# M182A.net
KiCad netlist of a schematic drawn in EAGLE
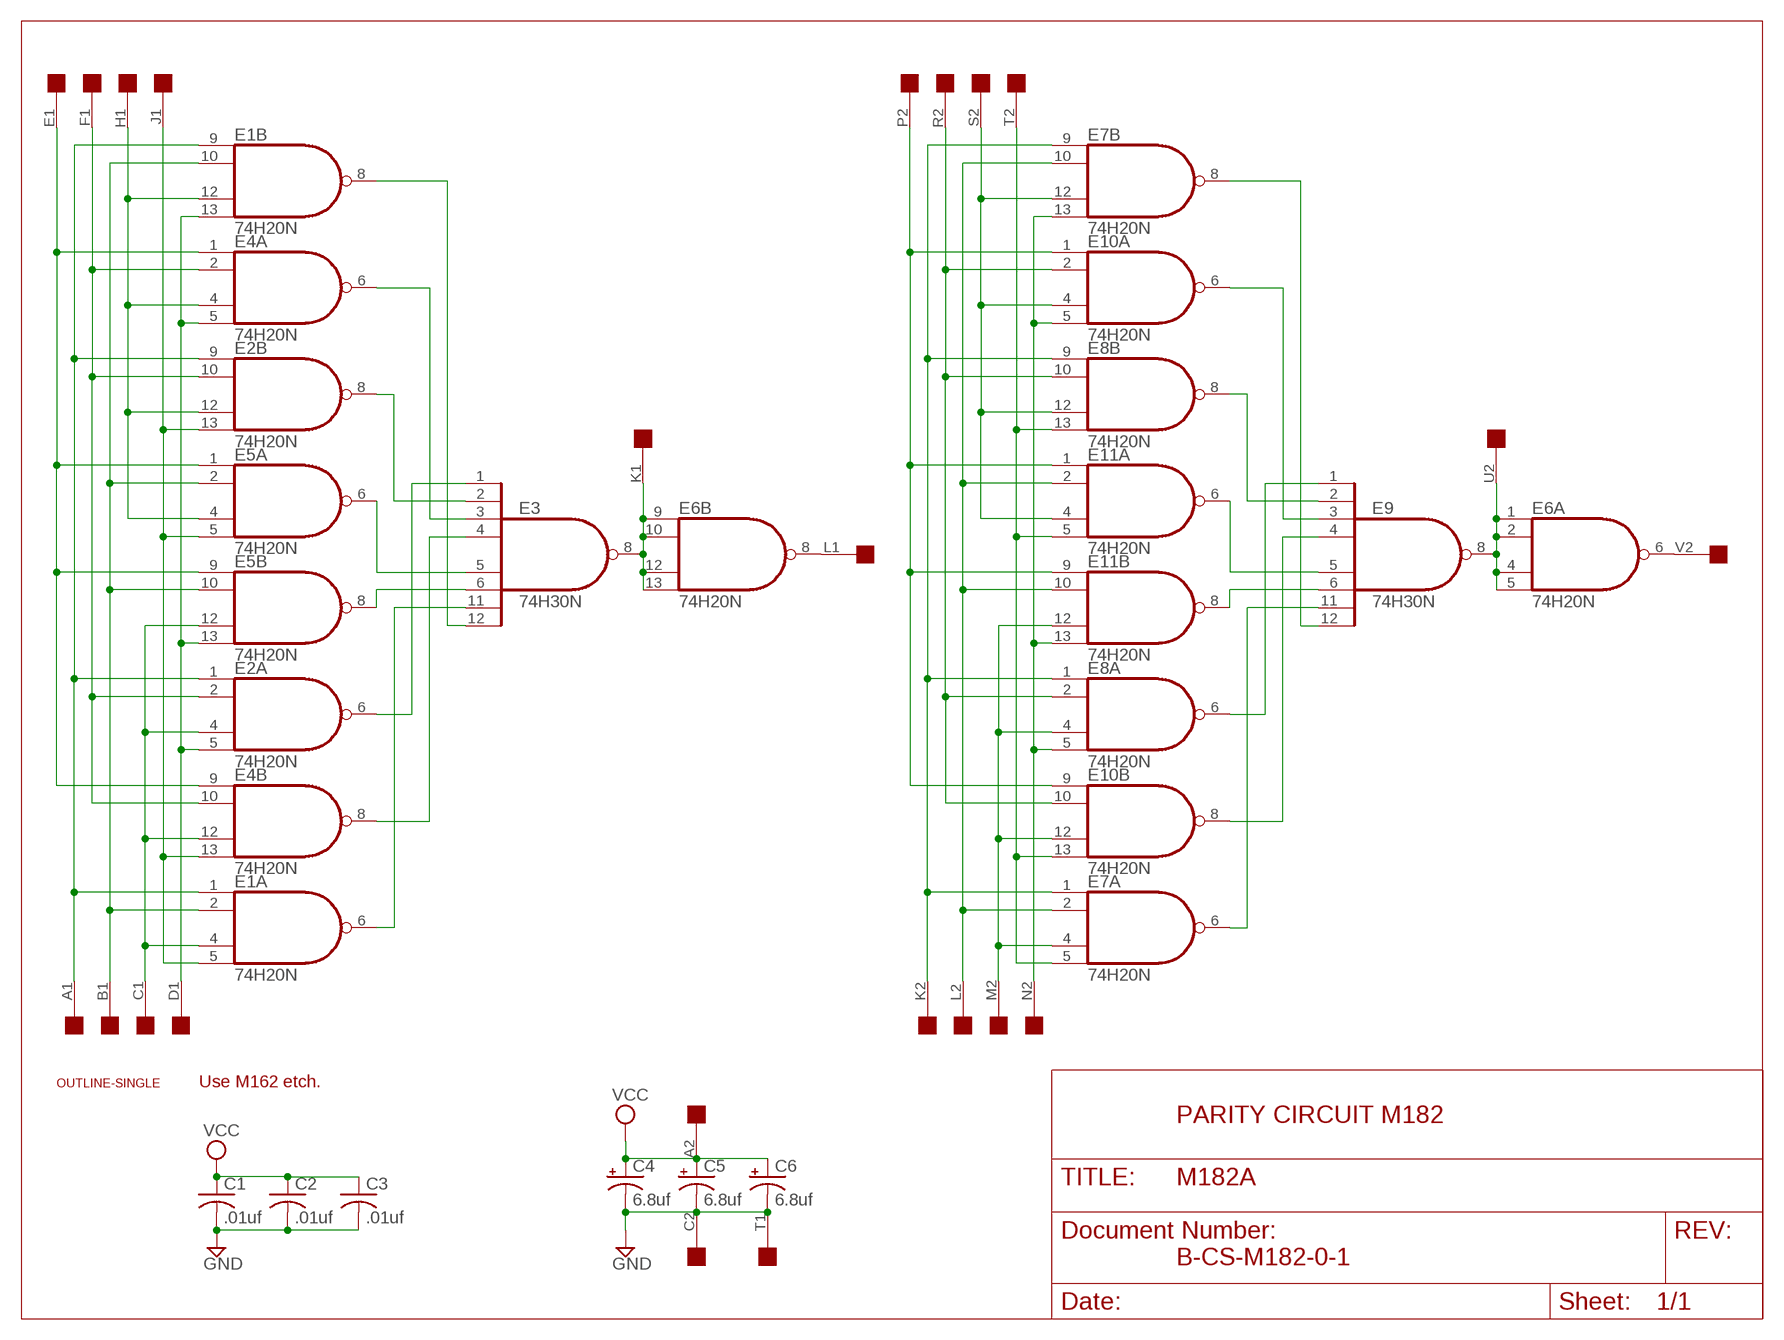
[diagram p0: schematic, sheet 1]

(export (version "E")
  (design (tool "Eeschema 10.0.6"))
  (components
    (comp (ref "C1")
      (value ".01uf")
      (footprint "eagle-import:C075-032X103")
      (libsource (lib "eagle-import") (part "C-US075-032X103"))
    )
    (comp (ref "C2")
      (value ".01uf")
      (footprint "eagle-import:C075-032X103")
      (libsource (lib "eagle-import") (part "C-US075-032X103"))
    )
    (comp (ref "C3")
      (value ".01uf")
      (footprint "eagle-import:C075-032X103")
      (libsource (lib "eagle-import") (part "C-US075-032X103"))
    )
    (comp (ref "C4")
      (value "6.8uf")
      (footprint "eagle-import:E15-5")
      (libsource (lib "eagle-import") (part "CPOL-USE15-5AXIAL"))
    )
    (comp (ref "C5")
      (value "6.8uf")
      (footprint "eagle-import:E15-5")
      (libsource (lib "eagle-import") (part "CPOL-USE15-5AXIAL"))
    )
    (comp (ref "C6")
      (value "6.8uf")
      (footprint "eagle-import:E15-5")
      (libsource (lib "eagle-import") (part "CPOL-USE15-5AXIAL"))
    )
    (comp (ref "E1")
      (value "74H20N")
      (footprint "eagle-import:DIL14")
      (libsource (lib "eagle-import") (part "7420NS"))
    )
    (comp (ref "E2")
      (value "74H20N")
      (footprint "eagle-import:DIL14")
      (libsource (lib "eagle-import") (part "7420NS"))
    )
    (comp (ref "E3")
      (value "74H30N")
      (footprint "eagle-import:DIL14")
      (libsource (lib "eagle-import") (part "7430N"))
    )
    (comp (ref "E4")
      (value "74H20N")
      (footprint "eagle-import:DIL14")
      (libsource (lib "eagle-import") (part "7420NS"))
    )
    (comp (ref "E5")
      (value "74H20N")
      (footprint "eagle-import:DIL14")
      (libsource (lib "eagle-import") (part "7420NS"))
    )
    (comp (ref "E6")
      (value "74H20N")
      (footprint "eagle-import:DIL14")
      (libsource (lib "eagle-import") (part "7420NS"))
    )
    (comp (ref "E7")
      (value "74H20N")
      (footprint "eagle-import:DIL14")
      (libsource (lib "eagle-import") (part "7420NS"))
    )
    (comp (ref "E8")
      (value "74H20N")
      (footprint "eagle-import:DIL14")
      (libsource (lib "eagle-import") (part "7420NS"))
    )
    (comp (ref "E9")
      (value "74H30N")
      (footprint "eagle-import:DIL14")
      (libsource (lib "eagle-import") (part "7430N"))
    )
    (comp (ref "E10")
      (value "74H20N")
      (footprint "eagle-import:DIL14")
      (libsource (lib "eagle-import") (part "7420NS"))
    )
    (comp (ref "E11")
      (value "74H20N")
      (footprint "eagle-import:DIL14")
      (libsource (lib "eagle-import") (part "7420NS"))
    )
    (comp (ref "U$1")
      (value "OUTLINE-SINGLE")
      (footprint "eagle-import:SINGLE")
      (libsource (lib "eagle-import") (part "OUTLINE-SINGLE"))
    )
    (comp (ref "U$2")
      (value "EDGE-2CONNECTOR")
      (footprint "eagle-import:EDGE-CON2")
      (libsource (lib "eagle-import") (part "EDGE-2CONNECTOR"))
    )
  )
  (nets
    (net (code "1") (name "GND") (class "Default")
      (node (ref "C1") (pin "2") (pinfunction "2_2") (pintype "passive"))
      (node (ref "C2") (pin "2") (pinfunction "2_2") (pintype "passive"))
      (node (ref "C3") (pin "2") (pinfunction "2_2") (pintype "passive"))
      (node (ref "C4") (pin "-") (pinfunction "-_-") (pintype "passive"))
      (node (ref "C5") (pin "-") (pinfunction "-_-") (pintype "passive"))
      (node (ref "C6") (pin "-") (pinfunction "-_-") (pintype "passive"))
      (node (ref "U$2") (pin "C2") (pinfunction "1_C2") (pintype "bidirectional"))
      (node (ref "U$2") (pin "T1") (pinfunction "1_T1") (pintype "bidirectional"))
    )
    (net (code "2") (name "Net-(E1C-I0)") (class "Default")
      (node (ref "E1") (pin "1") (pinfunction "I0_1") (pintype "input"))
      (node (ref "E1") (pin "9") (pinfunction "I0_9") (pintype "input"))
      (node (ref "E2") (pin "1") (pinfunction "I0_1") (pintype "input"))
      (node (ref "E2") (pin "9") (pinfunction "I0_9") (pintype "input"))
      (node (ref "U$2") (pin "A1") (pinfunction "1_A1") (pintype "bidirectional"))
    )
    (net (code "3") (name "Net-(E1C-I1)") (class "Default")
      (node (ref "E1") (pin "10") (pinfunction "I1_10") (pintype "input"))
      (node (ref "E1") (pin "2") (pinfunction "I1_2") (pintype "input"))
      (node (ref "E5") (pin "10") (pinfunction "I1_10") (pintype "input"))
      (node (ref "E5") (pin "2") (pinfunction "I1_2") (pintype "input"))
      (node (ref "U$2") (pin "B1") (pinfunction "1_B1") (pintype "bidirectional"))
    )
    (net (code "4") (name "Net-(E1C-I2)") (class "Default")
      (node (ref "E1") (pin "4") (pinfunction "I2_4") (pintype "input"))
      (node (ref "E2") (pin "4") (pinfunction "I2_4") (pintype "input"))
      (node (ref "E4") (pin "12") (pinfunction "I2_12") (pintype "input"))
      (node (ref "E5") (pin "12") (pinfunction "I2_12") (pintype "input"))
      (node (ref "U$2") (pin "C1") (pinfunction "1_C1") (pintype "bidirectional"))
    )
    (net (code "5") (name "Net-(E1C-I3)") (class "Default")
      (node (ref "E1") (pin "5") (pinfunction "I3_5") (pintype "input"))
      (node (ref "E2") (pin "13") (pinfunction "I3_13") (pintype "input"))
      (node (ref "E4") (pin "13") (pinfunction "I3_13") (pintype "input"))
      (node (ref "E5") (pin "5") (pinfunction "I3_5") (pintype "input"))
      (node (ref "U$2") (pin "J1") (pinfunction "1_J1") (pintype "bidirectional"))
    )
    (net (code "6") (name "Net-(E1C-O)") (class "Default")
      (node (ref "E1") (pin "6") (pinfunction "O_6") (pintype "output"))
      (node (ref "E3") (pin "11") (pinfunction "I6_11") (pintype "input"))
    )
    (net (code "7") (name "Net-(E1D-I2)") (class "Default")
      (node (ref "E1") (pin "12") (pinfunction "I2_12") (pintype "input"))
      (node (ref "E2") (pin "12") (pinfunction "I2_12") (pintype "input"))
      (node (ref "E4") (pin "4") (pinfunction "I2_4") (pintype "input"))
      (node (ref "E5") (pin "4") (pinfunction "I2_4") (pintype "input"))
      (node (ref "U$2") (pin "H1") (pinfunction "1_H1") (pintype "bidirectional"))
    )
    (net (code "8") (name "Net-(E1D-I3)") (class "Default")
      (node (ref "E1") (pin "13") (pinfunction "I3_13") (pintype "input"))
      (node (ref "E2") (pin "5") (pinfunction "I3_5") (pintype "input"))
      (node (ref "E4") (pin "5") (pinfunction "I3_5") (pintype "input"))
      (node (ref "E5") (pin "13") (pinfunction "I3_13") (pintype "input"))
      (node (ref "U$2") (pin "D1") (pinfunction "1_D1") (pintype "bidirectional"))
    )
    (net (code "9") (name "Net-(E1D-O)") (class "Default")
      (node (ref "E1") (pin "8") (pinfunction "O_8") (pintype "output"))
      (node (ref "E3") (pin "12") (pinfunction "I7_12") (pintype "input"))
    )
    (net (code "10") (name "Net-(E2C-I1)") (class "Default")
      (node (ref "E2") (pin "10") (pinfunction "I1_10") (pintype "input"))
      (node (ref "E2") (pin "2") (pinfunction "I1_2") (pintype "input"))
      (node (ref "E4") (pin "10") (pinfunction "I1_10") (pintype "input"))
      (node (ref "E4") (pin "2") (pinfunction "I1_2") (pintype "input"))
      (node (ref "U$2") (pin "F1") (pinfunction "1_F1") (pintype "bidirectional"))
    )
    (net (code "11") (name "Net-(E2C-O)") (class "Default")
      (node (ref "E2") (pin "6") (pinfunction "O_6") (pintype "output"))
      (node (ref "E3") (pin "1") (pinfunction "I0_1") (pintype "input"))
    )
    (net (code "12") (name "Net-(E2D-O)") (class "Default")
      (node (ref "E2") (pin "8") (pinfunction "O_8") (pintype "output"))
      (node (ref "E3") (pin "2") (pinfunction "I1_2") (pintype "input"))
    )
    (net (code "13") (name "Net-(E3A-I2)") (class "Default")
      (node (ref "E3") (pin "3") (pinfunction "I2_3") (pintype "input"))
      (node (ref "E4") (pin "6") (pinfunction "O_6") (pintype "output"))
    )
    (net (code "14") (name "Net-(E3A-I3)") (class "Default")
      (node (ref "E3") (pin "4") (pinfunction "I3_4") (pintype "input"))
      (node (ref "E4") (pin "8") (pinfunction "O_8") (pintype "output"))
    )
    (net (code "15") (name "Net-(E3A-I4)") (class "Default")
      (node (ref "E3") (pin "5") (pinfunction "I4_5") (pintype "input"))
      (node (ref "E5") (pin "6") (pinfunction "O_6") (pintype "output"))
    )
    (net (code "16") (name "Net-(E3A-I5)") (class "Default")
      (node (ref "E3") (pin "6") (pinfunction "I5_6") (pintype "input"))
      (node (ref "E5") (pin "8") (pinfunction "O_8") (pintype "output"))
    )
    (net (code "17") (name "Net-(E3A-O)") (class "Default")
      (node (ref "E3") (pin "8") (pinfunction "O_8") (pintype "output"))
      (node (ref "E6") (pin "10") (pinfunction "I1_10") (pintype "input"))
      (node (ref "E6") (pin "12") (pinfunction "I2_12") (pintype "input"))
      (node (ref "E6") (pin "13") (pinfunction "I3_13") (pintype "input"))
      (node (ref "E6") (pin "9") (pinfunction "I0_9") (pintype "input"))
      (node (ref "U$2") (pin "K1") (pinfunction "1_K1") (pintype "bidirectional"))
    )
    (net (code "18") (name "Net-(E4C-I0)") (class "Default")
      (node (ref "E4") (pin "1") (pinfunction "I0_1") (pintype "input"))
      (node (ref "E4") (pin "9") (pinfunction "I0_9") (pintype "input"))
      (node (ref "E5") (pin "1") (pinfunction "I0_1") (pintype "input"))
      (node (ref "E5") (pin "9") (pinfunction "I0_9") (pintype "input"))
      (node (ref "U$2") (pin "E1") (pinfunction "1_E1") (pintype "bidirectional"))
    )
    (net (code "19") (name "Net-(E6C-I0)") (class "Default")
      (node (ref "E6") (pin "1") (pinfunction "I0_1") (pintype "input"))
      (node (ref "E6") (pin "2") (pinfunction "I1_2") (pintype "input"))
      (node (ref "E6") (pin "4") (pinfunction "I2_4") (pintype "input"))
      (node (ref "E6") (pin "5") (pinfunction "I3_5") (pintype "input"))
      (node (ref "E9") (pin "8") (pinfunction "O_8") (pintype "output"))
      (node (ref "U$2") (pin "U2") (pinfunction "1_U2") (pintype "bidirectional"))
    )
    (net (code "20") (name "Net-(E6C-O)") (class "Default")
      (node (ref "E6") (pin "6") (pinfunction "O_6") (pintype "output"))
      (node (ref "U$2") (pin "V2") (pinfunction "1_V2") (pintype "bidirectional"))
    )
    (net (code "21") (name "Net-(E6D-O)") (class "Default")
      (node (ref "E6") (pin "8") (pinfunction "O_8") (pintype "output"))
      (node (ref "U$2") (pin "L1") (pinfunction "1_L1") (pintype "bidirectional"))
    )
    (net (code "22") (name "Net-(E7C-I0)") (class "Default")
      (node (ref "E7") (pin "1") (pinfunction "I0_1") (pintype "input"))
      (node (ref "E7") (pin "9") (pinfunction "I0_9") (pintype "input"))
      (node (ref "E8") (pin "1") (pinfunction "I0_1") (pintype "input"))
      (node (ref "E8") (pin "9") (pinfunction "I0_9") (pintype "input"))
      (node (ref "U$2") (pin "K2") (pinfunction "1_K2") (pintype "bidirectional"))
    )
    (net (code "23") (name "Net-(E7C-O)") (class "Default")
      (node (ref "E7") (pin "6") (pinfunction "O_6") (pintype "output"))
      (node (ref "E9") (pin "11") (pinfunction "I6_11") (pintype "input"))
    )
    (net (code "24") (name "Net-(E7D-O)") (class "Default")
      (node (ref "E7") (pin "8") (pinfunction "O_8") (pintype "output"))
      (node (ref "E9") (pin "12") (pinfunction "I7_12") (pintype "input"))
    )
    (net (code "25") (name "Net-(E8C-O)") (class "Default")
      (node (ref "E8") (pin "6") (pinfunction "O_6") (pintype "output"))
      (node (ref "E9") (pin "1") (pinfunction "I0_1") (pintype "input"))
    )
    (net (code "26") (name "Net-(E8D-O)") (class "Default")
      (node (ref "E8") (pin "8") (pinfunction "O_8") (pintype "output"))
      (node (ref "E9") (pin "2") (pinfunction "I1_2") (pintype "input"))
    )
    (net (code "27") (name "Net-(E10C-I0)") (class "Default")
      (node (ref "E10") (pin "1") (pinfunction "I0_1") (pintype "input"))
      (node (ref "E10") (pin "9") (pinfunction "I0_9") (pintype "input"))
      (node (ref "E11") (pin "1") (pinfunction "I0_1") (pintype "input"))
      (node (ref "E11") (pin "9") (pinfunction "I0_9") (pintype "input"))
      (node (ref "U$2") (pin "P2") (pinfunction "1_P2") (pintype "bidirectional"))
    )
    (net (code "28") (name "Net-(E10C-I1)") (class "Default")
      (node (ref "E10") (pin "10") (pinfunction "I1_10") (pintype "input"))
      (node (ref "E10") (pin "2") (pinfunction "I1_2") (pintype "input"))
      (node (ref "E8") (pin "10") (pinfunction "I1_10") (pintype "input"))
      (node (ref "E8") (pin "2") (pinfunction "I1_2") (pintype "input"))
      (node (ref "U$2") (pin "R2") (pinfunction "1_R2") (pintype "bidirectional"))
    )
    (net (code "29") (name "Net-(E10C-I2)") (class "Default")
      (node (ref "E10") (pin "4") (pinfunction "I2_4") (pintype "input"))
      (node (ref "E11") (pin "4") (pinfunction "I2_4") (pintype "input"))
      (node (ref "E7") (pin "12") (pinfunction "I2_12") (pintype "input"))
      (node (ref "E8") (pin "12") (pinfunction "I2_12") (pintype "input"))
      (node (ref "U$2") (pin "S2") (pinfunction "1_S2") (pintype "bidirectional"))
    )
    (net (code "30") (name "Net-(E10C-I3)") (class "Default")
      (node (ref "E10") (pin "5") (pinfunction "I3_5") (pintype "input"))
      (node (ref "E11") (pin "13") (pinfunction "I3_13") (pintype "input"))
      (node (ref "E7") (pin "13") (pinfunction "I3_13") (pintype "input"))
      (node (ref "E8") (pin "5") (pinfunction "I3_5") (pintype "input"))
      (node (ref "U$2") (pin "N2") (pinfunction "1_N2") (pintype "bidirectional"))
    )
    (net (code "31") (name "Net-(E10C-O)") (class "Default")
      (node (ref "E10") (pin "6") (pinfunction "O_6") (pintype "output"))
      (node (ref "E9") (pin "3") (pinfunction "I2_3") (pintype "input"))
    )
    (net (code "32") (name "Net-(E10D-I2)") (class "Default")
      (node (ref "E10") (pin "12") (pinfunction "I2_12") (pintype "input"))
      (node (ref "E11") (pin "12") (pinfunction "I2_12") (pintype "input"))
      (node (ref "E7") (pin "4") (pinfunction "I2_4") (pintype "input"))
      (node (ref "E8") (pin "4") (pinfunction "I2_4") (pintype "input"))
      (node (ref "U$2") (pin "M2") (pinfunction "1_M2") (pintype "bidirectional"))
    )
    (net (code "33") (name "Net-(E10D-I3)") (class "Default")
      (node (ref "E10") (pin "13") (pinfunction "I3_13") (pintype "input"))
      (node (ref "E11") (pin "5") (pinfunction "I3_5") (pintype "input"))
      (node (ref "E7") (pin "5") (pinfunction "I3_5") (pintype "input"))
      (node (ref "E8") (pin "13") (pinfunction "I3_13") (pintype "input"))
      (node (ref "U$2") (pin "T2") (pinfunction "1_T2") (pintype "bidirectional"))
    )
    (net (code "34") (name "Net-(E10D-O)") (class "Default")
      (node (ref "E10") (pin "8") (pinfunction "O_8") (pintype "output"))
      (node (ref "E9") (pin "4") (pinfunction "I3_4") (pintype "input"))
    )
    (net (code "35") (name "Net-(E11C-I1)") (class "Default")
      (node (ref "E11") (pin "10") (pinfunction "I1_10") (pintype "input"))
      (node (ref "E11") (pin "2") (pinfunction "I1_2") (pintype "input"))
      (node (ref "E7") (pin "10") (pinfunction "I1_10") (pintype "input"))
      (node (ref "E7") (pin "2") (pinfunction "I1_2") (pintype "input"))
      (node (ref "U$2") (pin "L2") (pinfunction "1_L2") (pintype "bidirectional"))
    )
    (net (code "36") (name "Net-(E11C-O)") (class "Default")
      (node (ref "E11") (pin "6") (pinfunction "O_6") (pintype "output"))
      (node (ref "E9") (pin "5") (pinfunction "I4_5") (pintype "input"))
    )
    (net (code "37") (name "Net-(E11D-O)") (class "Default")
      (node (ref "E11") (pin "8") (pinfunction "O_8") (pintype "output"))
      (node (ref "E9") (pin "6") (pinfunction "I5_6") (pintype "input"))
    )
    (net (code "38") (name "VCC") (class "Default")
      (node (ref "C1") (pin "1") (pinfunction "1_1") (pintype "passive"))
      (node (ref "C2") (pin "1") (pinfunction "1_1") (pintype "passive"))
      (node (ref "C3") (pin "1") (pinfunction "1_1") (pintype "passive"))
      (node (ref "C4") (pin "+") (pinfunction "+_+") (pintype "passive"))
      (node (ref "C5") (pin "+") (pinfunction "+_+") (pintype "passive"))
      (node (ref "C6") (pin "+") (pinfunction "+_+") (pintype "passive"))
      (node (ref "U$2") (pin "A2") (pinfunction "1_A2") (pintype "bidirectional"))
    )
  )
)
